# MCU.net
KiCad netlist of a schematic drawn in Altium Designer
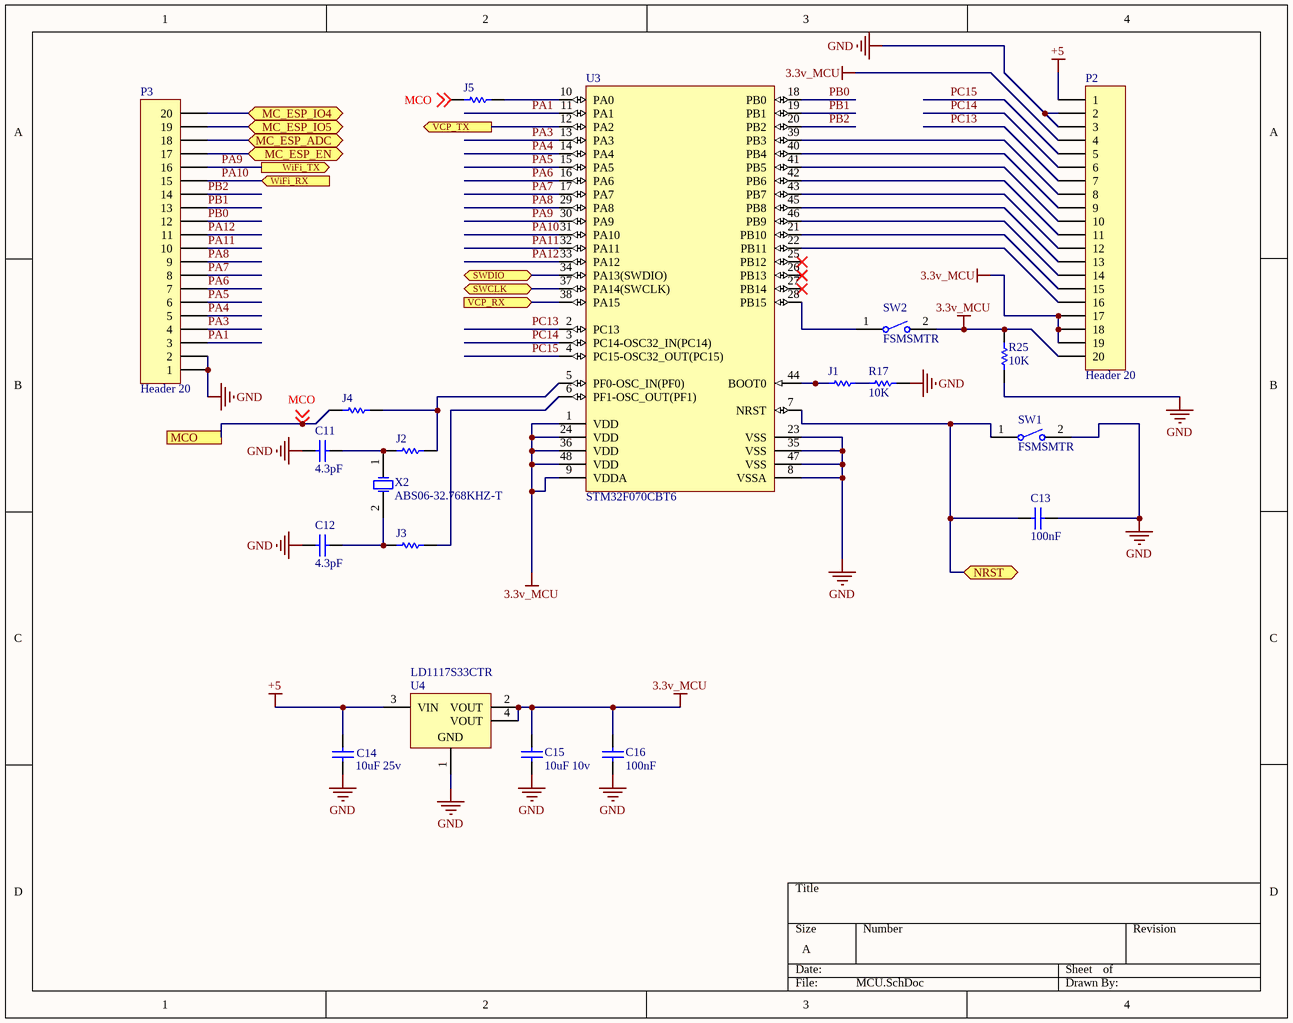
[diagram p0: MCU.SchDoc]

(export (version "E")
  (design (tool "Eeschema 10.0.6"))
  (components
    (comp (ref "C11")
      (value "4.3pF")
      (footprint "CAPC0603(1608)100_L")
      (description "CAP 4.3pF 25V ±0.5pF 0603 (1608 Metric) Thickness 1mm SMD")
      (fields (field (name "TOLERANCE") "Â±0.5pF"))
      (libsource (lib "Altium Content Vault") (part "CAP"))
    )
    (comp (ref "C12")
      (value "4.3pF")
      (footprint "CAPC0603(1608)100_L")
      (description "CAP 4.3pF 25V ±0.5pF 0603 (1608 Metric) Thickness 1mm SMD")
      (fields (field (name "TOLERANCE") "Â±0.5pF"))
      (libsource (lib "Altium Content Vault") (part "CAP"))
    )
    (comp (ref "C13")
      (value "100nF")
      (footprint "CAPC0603(1608)100_L")
      (description "CAP 100nF 16V ±5% 0603 (1608 Metric) Thickness 1mm SMD")
      (fields (field (name "TOLERANCE") "Â±5%"))
      (libsource (lib "Altium Content Vault") (part "CAP"))
    )
    (comp (ref "C14")
      (value "10uF 25v")
      (footprint "CAPC0805(2012)145_L")
      (description "CAP 10uF 25V ±10% 0805 (2012 Metric) Thickness 1.45mm SMD")
      (fields (field (name "TOLERANCE") "Â±10%"))
      (libsource (lib "Altium Content Vault") (part "CAP"))
    )
    (comp (ref "C15")
      (value "10uF 10v")
      (footprint "CAPC0805(2012)145_L")
      (description "CAP 10uF 10V -20% to +80% 0805 (2012 Metric) Thickness 1.45mm SMD")
      (fields (field (name "TOLERANCE") "-20% to +80%"))
      (libsource (lib "Altium Content Vault") (part "CAP"))
    )
    (comp (ref "C16")
      (value "100nF")
      (footprint "CAPC0603(1608)100_L")
      (description "CAP 100nF 16V ±5% 0603 (1608 Metric) Thickness 1mm SMD")
      (fields (field (name "TOLERANCE") "Â±5%"))
      (libsource (lib "Altium Content Vault") (part "CAP"))
    )
    (comp (ref "J1")
      (value "~")
      (footprint "RESC1608X55X30LL10T20_A")
      (description "Chip Resistor, 0 Ohm, +/- 5%, 100 mW, -55 to 155 degC, 0603 (1608 Metric), RoHS, Tape and Reel")
      (fields (field (name "TOLERANCE") "Jumper") (field (name "MANUFACTURER") "Rohm"))
      (libsource (lib "Altium Content Vault") (part "RES-2"))
    )
    (comp (ref "J2")
      (value "~")
      (footprint "RESC1608X55X30LL10T20_A")
      (description "Chip Resistor, 0 Ohm, +/- 5%, 100 mW, -55 to 155 degC, 0603 (1608 Metric), RoHS, Tape and Reel")
      (fields (field (name "TOLERANCE") "Jumper") (field (name "MANUFACTURER") "Rohm"))
      (libsource (lib "Altium Content Vault") (part "RES-2"))
    )
    (comp (ref "J3")
      (value "~")
      (footprint "RESC1608X55X30LL10T20_A")
      (description "Chip Resistor, 0 Ohm, +/- 5%, 100 mW, -55 to 155 degC, 0603 (1608 Metric), RoHS, Tape and Reel")
      (fields (field (name "TOLERANCE") "Jumper") (field (name "MANUFACTURER") "Rohm"))
      (libsource (lib "Altium Content Vault") (part "RES-2"))
    )
    (comp (ref "J4")
      (value "~")
      (footprint "RESC1608X55X30LL10T20_A")
      (description "Chip Resistor, 0 Ohm, +/- 5%, 100 mW, -55 to 155 degC, 0603 (1608 Metric), RoHS, Tape and Reel")
      (fields (field (name "TOLERANCE") "Jumper") (field (name "MANUFACTURER") "Rohm"))
      (libsource (lib "Altium Content Vault") (part "RES-2"))
    )
    (comp (ref "J5")
      (value "~")
      (footprint "RESC1608X55X30LL10T20_A")
      (description "Chip Resistor, 0 Ohm, +/- 5%, 100 mW, -55 to 155 degC, 0603 (1608 Metric), RoHS, Tape and Reel")
      (fields (field (name "TOLERANCE") "Jumper") (field (name "MANUFACTURER") "Rohm"))
      (libsource (lib "Altium Content Vault") (part "RES-2"))
    )
    (comp (ref "P2")
      (value "Header 20")
      (footprint "HDR1X20")
      (description "Header, 20-Pin")
      (fields (field (name "PUBLISHER") "Altium Limited"))
      (libsource (lib "") (part "Header 20_1"))
    )
    (comp (ref "P3")
      (value "Header 20")
      (footprint "HDR1X20")
      (description "Header, 20-Pin")
      (fields (field (name "PUBLISHER") "Altium Limited"))
      (libsource (lib "Miscellaneous Connectors") (part "Header 20"))
    )
    (comp (ref "R17")
      (value "10K")
      (footprint "RESC1609X55X30LL15T15")
      (description "Chip Resistor, 10 KOhm, +/- 1%, 0.1 W, -55 to 155 degC, 0603 (1608 Metric), RoHS, Tape and Reel")
      (fields (field (name "TOLERANCE") "1%") (field (name "MANUFACTURER") "Panasonic"))
      (libsource (lib "Altium Content Vault") (part "RES-2"))
    )
    (comp (ref "R25")
      (value "10K")
      (footprint "RESC1609X55X30LL15T15")
      (description "Chip Resistor, 10 KOhm, +/- 1%, 0.1 W, -55 to 155 degC, 0603 (1608 Metric), RoHS, Tape and Reel")
      (fields (field (name "TOLERANCE") "1%") (field (name "MANUFACTURER") "Panasonic"))
      (libsource (lib "Altium Content Vault") (part "RES-2"))
    )
    (comp (ref "SW1")
      (value "FSMSMTR")
      (footprint "TECO-FSMSMTR_V")
      (description "FSMSM Push Button Switch, 50 mA, -35 to 85 degC, 2-Pin SMD, RoHS, Tape and Reel")
      (fields (field (name "MANUFACTURER") "TE Connectivity"))
      (libsource (lib "Altium Content Vault") (part "SW-SPST-2_C"))
    )
    (comp (ref "SW2")
      (value "FSMSMTR")
      (footprint "TECO-FSMSMTR_V")
      (description "FSMSM Push Button Switch, 50 mA, -35 to 85 degC, 2-Pin SMD, RoHS, Tape and Reel")
      (fields (field (name "MANUFACTURER") "TE Connectivity"))
      (libsource (lib "Altium Content Vault") (part "SW-SPST-2_C"))
    )
    (comp (ref "U3")
      (value "STM32F070CBT6")
      (footprint "STM-LQFP48_N")
      (libsource (lib "Altium Content Vault") (part "MC-ARM-STM32F070-LQFP48"))
    )
    (comp (ref "U4")
      (value "LD1117S33CTR")
      (footprint "SOT-223_N")
      (description "Fixed Low Drop Positive Voltage Regulator, 3.3V, 4-Pin SOT-223, Tape and Reel")
      (libsource (lib "Altium Content Vault") (part "PM-REG-LD1117-SOT4"))
    )
    (comp (ref "X2")
      (value "ABS06-32.768KHZ-T")
      (footprint "ABRA-ABS06-2_V")
      (description "Low Profile Crystal, 32.768 KHz, -40 to 85 degC, 2-Pin SMD, RoHS, Tape and Reel")
      (fields (field (name "TOLERANCE") "20PPM") (field (name "MANUFACTURER") "ABRACON"))
      (libsource (lib "Altium Content Vault") (part "XTAL_1-2-2"))
    )
  )
  (nets
    (net (code "1") (name "+5") (class "Default")
      (node (ref "C14") (pin "2") (pinfunction "2_2") (pintype "passive"))
      (node (ref "P2") (pin "1") (pinfunction "1_1") (pintype "passive"))
      (node (ref "U4") (pin "3") (pinfunction "VIN_3") (pintype "power_in"))
    )
    (net (code "2") (name "/MC_ESP_ADC") (class "Default")
      (node (ref "P3") (pin "18") (pinfunction "18_18") (pintype "passive"))
    )
    (net (code "3") (name "/MC_ESP_EN") (class "Default")
      (node (ref "P3") (pin "17") (pinfunction "17_17") (pintype "passive"))
    )
    (net (code "4") (name "/MC_ESP_IO4") (class "Default")
      (node (ref "P3") (pin "20") (pinfunction "20_20") (pintype "passive"))
    )
    (net (code "5") (name "/MC_ESP_IO5") (class "Default")
      (node (ref "P3") (pin "19") (pinfunction "19_19") (pintype "passive"))
    )
    (net (code "6") (name "/NRST") (class "Default")
      (node (ref "C13") (pin "2") (pinfunction "2_2") (pintype "passive"))
      (node (ref "SW1") (pin "1") (pinfunction "1_1") (pintype "passive"))
      (node (ref "U3") (pin "7") (pinfunction "NRST_7") (pintype "bidirectional"))
    )
    (net (code "7") (name "/PA1") (class "Default")
      (node (ref "P3") (pin "3") (pinfunction "3_3") (pintype "passive"))
      (node (ref "U3") (pin "11") (pinfunction "PA1_11") (pintype "bidirectional"))
    )
    (net (code "8") (name "/PA3") (class "Default")
      (node (ref "P3") (pin "4") (pinfunction "4_4") (pintype "passive"))
      (node (ref "U3") (pin "13") (pinfunction "PA3_13") (pintype "bidirectional"))
    )
    (net (code "9") (name "/PA4") (class "Default")
      (node (ref "P3") (pin "5") (pinfunction "5_5") (pintype "passive"))
      (node (ref "U3") (pin "14") (pinfunction "PA4_14") (pintype "bidirectional"))
    )
    (net (code "10") (name "/PA5") (class "Default")
      (node (ref "P3") (pin "6") (pinfunction "6_6") (pintype "passive"))
      (node (ref "U3") (pin "15") (pinfunction "PA5_15") (pintype "bidirectional"))
    )
    (net (code "11") (name "/PA6") (class "Default")
      (node (ref "P3") (pin "7") (pinfunction "7_7") (pintype "passive"))
      (node (ref "U3") (pin "16") (pinfunction "PA6_16") (pintype "bidirectional"))
    )
    (net (code "12") (name "/PA7") (class "Default")
      (node (ref "P3") (pin "8") (pinfunction "8_8") (pintype "passive"))
      (node (ref "U3") (pin "17") (pinfunction "PA7_17") (pintype "bidirectional"))
    )
    (net (code "13") (name "/PA8") (class "Default")
      (node (ref "P3") (pin "9") (pinfunction "9_9") (pintype "passive"))
      (node (ref "U3") (pin "29") (pinfunction "PA8_29") (pintype "bidirectional"))
    )
    (net (code "14") (name "/PA9") (class "Default")
      (node (ref "P3") (pin "16") (pinfunction "16_16") (pintype "passive"))
      (node (ref "U3") (pin "30") (pinfunction "PA9_30") (pintype "bidirectional"))
    )
    (net (code "15") (name "/PA10") (class "Default")
      (node (ref "P3") (pin "15") (pinfunction "15_15") (pintype "passive"))
      (node (ref "U3") (pin "31") (pinfunction "PA10_31") (pintype "bidirectional"))
    )
    (net (code "16") (name "/PA11") (class "Default")
      (node (ref "P3") (pin "10") (pinfunction "10_10") (pintype "passive"))
      (node (ref "U3") (pin "32") (pinfunction "PA11_32") (pintype "bidirectional"))
    )
    (net (code "17") (name "/PA12") (class "Default")
      (node (ref "P3") (pin "11") (pinfunction "11_11") (pintype "passive"))
      (node (ref "U3") (pin "33") (pinfunction "PA12_33") (pintype "bidirectional"))
    )
    (net (code "18") (name "/PB0") (class "Default")
      (node (ref "P3") (pin "12") (pinfunction "12_12") (pintype "passive"))
      (node (ref "U3") (pin "18") (pinfunction "PB0_18") (pintype "bidirectional"))
    )
    (net (code "19") (name "/PB1") (class "Default")
      (node (ref "P3") (pin "13") (pinfunction "13_13") (pintype "passive"))
      (node (ref "U3") (pin "19") (pinfunction "PB1_19") (pintype "bidirectional"))
    )
    (net (code "20") (name "/PB2") (class "Default")
      (node (ref "P3") (pin "14") (pinfunction "14_14") (pintype "passive"))
      (node (ref "U3") (pin "20") (pinfunction "PB2_20") (pintype "bidirectional"))
    )
    (net (code "21") (name "/PC13") (class "Default")
      (node (ref "P2") (pin "7") (pinfunction "7_7") (pintype "passive"))
      (node (ref "U3") (pin "2") (pinfunction "PC13_2") (pintype "bidirectional"))
    )
    (net (code "22") (name "/PC14") (class "Default")
      (node (ref "P2") (pin "6") (pinfunction "6_6") (pintype "passive"))
      (node (ref "U3") (pin "3") (pinfunction "PC14-OSC32_IN(PC14)_3") (pintype "bidirectional"))
    )
    (net (code "23") (name "/PC15") (class "Default")
      (node (ref "P2") (pin "5") (pinfunction "5_5") (pintype "passive"))
      (node (ref "U3") (pin "4") (pinfunction "PC15-OSC32_OUT(PC15)_4") (pintype "bidirectional"))
    )
    (net (code "24") (name "/SWCLK") (class "Default")
      (node (ref "U3") (pin "37") (pinfunction "PA14(SWCLK)_37") (pintype "bidirectional"))
    )
    (net (code "25") (name "/SWDIO") (class "Default")
      (node (ref "U3") (pin "34") (pinfunction "PA13(SWDIO)_34") (pintype "bidirectional"))
    )
    (net (code "26") (name "/VCP_RX") (class "Default")
      (node (ref "U3") (pin "38") (pinfunction "PA15_38") (pintype "bidirectional"))
    )
    (net (code "27") (name "/VCP_TX") (class "Default")
      (node (ref "U3") (pin "12") (pinfunction "PA2_12") (pintype "bidirectional"))
    )
    (net (code "28") (name "3.3v_MCU") (class "Default")
      (node (ref "C15") (pin "2") (pinfunction "2_2") (pintype "passive"))
      (node (ref "C16") (pin "2") (pinfunction "2_2") (pintype "passive"))
      (node (ref "P2") (pin "17") (pinfunction "17_17") (pintype "passive"))
      (node (ref "P2") (pin "18") (pinfunction "18_18") (pintype "passive"))
      (node (ref "P2") (pin "19") (pinfunction "19_19") (pintype "passive"))
      (node (ref "P2") (pin "20") (pinfunction "20_20") (pintype "passive"))
      (node (ref "P2") (pin "4") (pinfunction "4_4") (pintype "passive"))
      (node (ref "R25") (pin "2") (pinfunction "2_2") (pintype "passive"))
      (node (ref "SW2") (pin "2") (pinfunction "2_2") (pintype "passive"))
      (node (ref "U3") (pin "1") (pinfunction "VDD_1") (pintype "power_in"))
      (node (ref "U3") (pin "24") (pinfunction "VDD_24") (pintype "power_in"))
      (node (ref "U3") (pin "36") (pinfunction "VDD_36") (pintype "power_in"))
      (node (ref "U3") (pin "48") (pinfunction "VDD_48") (pintype "power_in"))
      (node (ref "U3") (pin "9") (pinfunction "VDDA_9") (pintype "power_in"))
      (node (ref "U4") (pin "2") (pinfunction "VOUT_2") (pintype "power_in"))
      (node (ref "U4") (pin "4") (pinfunction "VOUT_4") (pintype "power_in"))
    )
    (net (code "29") (name "GND") (class "Default")
      (node (ref "C11") (pin "1") (pinfunction "1_1") (pintype "passive"))
      (node (ref "C12") (pin "1") (pinfunction "1_1") (pintype "passive"))
      (node (ref "C13") (pin "1") (pinfunction "1_1") (pintype "passive"))
      (node (ref "C14") (pin "1") (pinfunction "1_1") (pintype "passive"))
      (node (ref "C15") (pin "1") (pinfunction "1_1") (pintype "passive"))
      (node (ref "C16") (pin "1") (pinfunction "1_1") (pintype "passive"))
      (node (ref "P2") (pin "2") (pinfunction "2_2") (pintype "passive"))
      (node (ref "P2") (pin "3") (pinfunction "3_3") (pintype "passive"))
      (node (ref "P3") (pin "1") (pinfunction "1_1") (pintype "passive"))
      (node (ref "P3") (pin "2") (pinfunction "2_2") (pintype "passive"))
      (node (ref "R17") (pin "2") (pinfunction "2_2") (pintype "passive"))
      (node (ref "R25") (pin "1") (pinfunction "1_1") (pintype "passive"))
      (node (ref "SW1") (pin "2") (pinfunction "2_2") (pintype "passive"))
      (node (ref "U3") (pin "23") (pinfunction "VSS_23") (pintype "power_in"))
      (node (ref "U3") (pin "35") (pinfunction "VSS_35") (pintype "power_in"))
      (node (ref "U3") (pin "47") (pinfunction "VSS_47") (pintype "power_in"))
      (node (ref "U3") (pin "8") (pinfunction "VSSA_8") (pintype "power_in"))
      (node (ref "U4") (pin "1") (pinfunction "GND_1") (pintype "power_in"))
    )
    (net (code "30") (name "MCO") (class "Default")
      (node (ref "J4") (pin "1") (pinfunction "1_1") (pintype "passive"))
      (node (ref "J5") (pin "1") (pinfunction "1_1") (pintype "passive"))
    )
    (net (code "31") (name "Net-(J1-Pad2)") (class "Default")
      (node (ref "J1") (pin "2") (pinfunction "2_2") (pintype "passive"))
      (node (ref "R17") (pin "1") (pinfunction "1_1") (pintype "passive"))
    )
    (net (code "32") (name "Net-(U3-BOOT0)") (class "Default")
      (node (ref "J1") (pin "1") (pinfunction "1_1") (pintype "passive"))
      (node (ref "U3") (pin "44") (pinfunction "BOOT0_44") (pintype "input"))
    )
    (net (code "33") (name "Net-(U3-PA0)") (class "Default")
      (node (ref "J5") (pin "2") (pinfunction "2_2") (pintype "passive"))
      (node (ref "U3") (pin "10") (pinfunction "PA0_10") (pintype "bidirectional"))
    )
    (net (code "34") (name "Net-(U3-PB3)") (class "Default")
      (node (ref "P2") (pin "8") (pinfunction "8_8") (pintype "passive"))
      (node (ref "U3") (pin "39") (pinfunction "PB3_39") (pintype "bidirectional"))
    )
    (net (code "35") (name "Net-(U3-PB4)") (class "Default")
      (node (ref "P2") (pin "9") (pinfunction "9_9") (pintype "passive"))
      (node (ref "U3") (pin "40") (pinfunction "PB4_40") (pintype "bidirectional"))
    )
    (net (code "36") (name "Net-(U3-PB5)") (class "Default")
      (node (ref "P2") (pin "10") (pinfunction "10_10") (pintype "passive"))
      (node (ref "U3") (pin "41") (pinfunction "PB5_41") (pintype "bidirectional"))
    )
    (net (code "37") (name "Net-(U3-PB6)") (class "Default")
      (node (ref "P2") (pin "11") (pinfunction "11_11") (pintype "passive"))
      (node (ref "U3") (pin "42") (pinfunction "PB6_42") (pintype "bidirectional"))
    )
    (net (code "38") (name "Net-(U3-PB7)") (class "Default")
      (node (ref "P2") (pin "12") (pinfunction "12_12") (pintype "passive"))
      (node (ref "U3") (pin "43") (pinfunction "PB7_43") (pintype "bidirectional"))
    )
    (net (code "39") (name "Net-(U3-PB8)") (class "Default")
      (node (ref "P2") (pin "13") (pinfunction "13_13") (pintype "passive"))
      (node (ref "U3") (pin "45") (pinfunction "PB8_45") (pintype "bidirectional"))
    )
    (net (code "40") (name "Net-(U3-PB9)") (class "Default")
      (node (ref "P2") (pin "14") (pinfunction "14_14") (pintype "passive"))
      (node (ref "U3") (pin "46") (pinfunction "PB9_46") (pintype "bidirectional"))
    )
    (net (code "41") (name "Net-(U3-PB10)") (class "Default")
      (node (ref "P2") (pin "15") (pinfunction "15_15") (pintype "passive"))
      (node (ref "U3") (pin "21") (pinfunction "PB10_21") (pintype "bidirectional"))
    )
    (net (code "42") (name "Net-(U3-PB11)") (class "Default")
      (node (ref "P2") (pin "16") (pinfunction "16_16") (pintype "passive"))
      (node (ref "U3") (pin "22") (pinfunction "PB11_22") (pintype "bidirectional"))
    )
    (net (code "43") (name "Net-(U3-PB15)") (class "Default")
      (node (ref "SW2") (pin "1") (pinfunction "1_1") (pintype "passive"))
      (node (ref "U3") (pin "28") (pinfunction "PB15_28") (pintype "bidirectional"))
    )
    (net (code "44") (name "Net-(U3-PF0-OSC_IN(PF0))") (class "Default")
      (node (ref "J2") (pin "2") (pinfunction "2_2") (pintype "passive"))
      (node (ref "J4") (pin "2") (pinfunction "2_2") (pintype "passive"))
      (node (ref "U3") (pin "5") (pinfunction "PF0-OSC_IN(PF0)_5") (pintype "bidirectional"))
    )
    (net (code "45") (name "Net-(U3-PF1-OSC_OUT(PF1))") (class "Default")
      (node (ref "J3") (pin "2") (pinfunction "2_2") (pintype "passive"))
      (node (ref "U3") (pin "6") (pinfunction "PF1-OSC_OUT(PF1)_6") (pintype "bidirectional"))
    )
    (net (code "46") (name "Net-(X2-X1)") (class "Default")
      (node (ref "C11") (pin "2") (pinfunction "2_2") (pintype "passive"))
      (node (ref "J2") (pin "1") (pinfunction "1_1") (pintype "passive"))
      (node (ref "X2") (pin "1") (pinfunction "X1_1") (pintype "passive"))
    )
    (net (code "47") (name "Net-(X2-X2)") (class "Default")
      (node (ref "C12") (pin "2") (pinfunction "2_2") (pintype "passive"))
      (node (ref "J3") (pin "1") (pinfunction "1_1") (pintype "passive"))
      (node (ref "X2") (pin "2") (pinfunction "X2_2") (pintype "passive"))
    )
    (net (code "48") (name "unconnected-(U3-PB12-Pad25)") (class "Default")
      (node (ref "U3") (pin "25") (pinfunction "PB12_25") (pintype "bidirectional+no_connect"))
    )
    (net (code "49") (name "unconnected-(U3-PB13-Pad26)") (class "Default")
      (node (ref "U3") (pin "26") (pinfunction "PB13_26") (pintype "bidirectional+no_connect"))
    )
    (net (code "50") (name "unconnected-(U3-PB14-Pad27)") (class "Default")
      (node (ref "U3") (pin "27") (pinfunction "PB14_27") (pintype "bidirectional+no_connect"))
    )
  )
)
